# panner.net
KiCad netlist of a schematic drawn in EAGLE
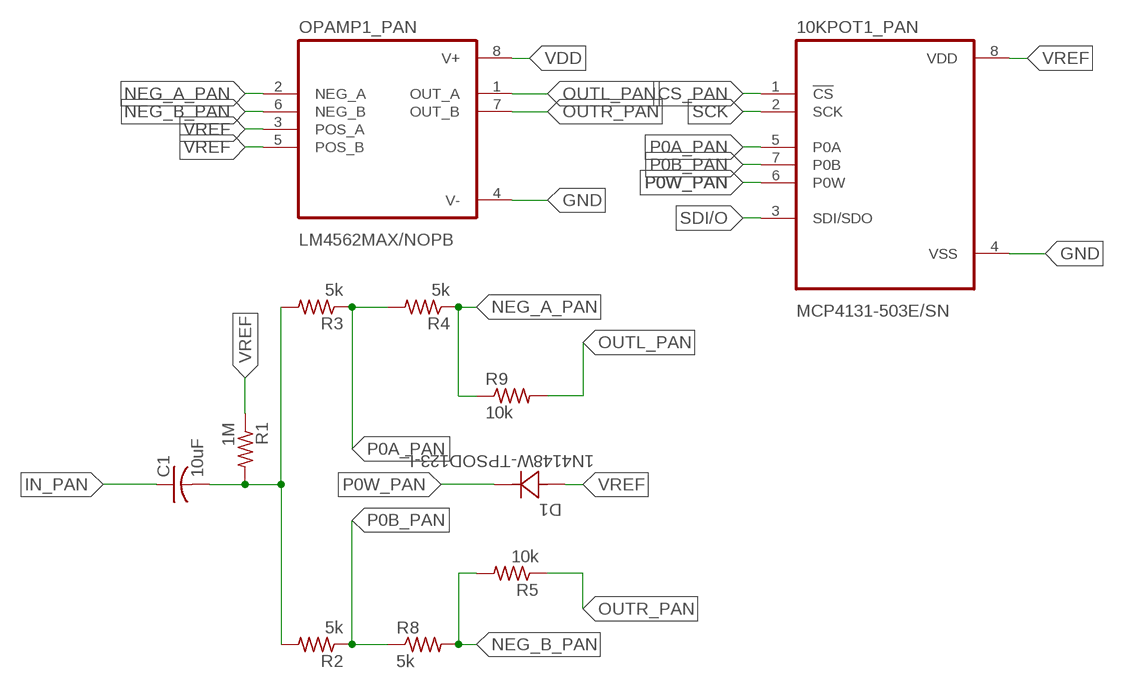
[diagram p0: schematic, sheet 1]

(export (version "E")
  (design (tool "Eeschema 10.0.6"))
  (components
    (comp (ref "10KPOT1_PAN")
      (value "MCP4131-503E/SN")
      (footprint "eagle-import:SOIC127P599X175-8N")
      (fields (field (name "MF") "Microchip") (field (name "SPICEPREFIX") "X"))
      (libsource (lib "eagle-import") (part "MCP4131-503E/SN"))
    )
    (comp (ref "C1")
      (value "10uF")
      (footprint "eagle-import:C0402")
      (libsource (lib "eagle-import") (part "C-USC0402"))
    )
    (comp (ref "D1")
      (value "1N4148W-TPSOD123-L")
      (footprint "eagle-import:SOD123-L")
      (fields (field (name "MF") "Micro Commercial") (field (name "MP") "1N4148W-TP"))
      (libsource (lib "eagle-import") (part "1N4148W-TPSOD123-L"))
    )
    (comp (ref "OPAMP1_PAN")
      (value "LM4562MAX/NOPB")
      (footprint "eagle-import:SOIC127P599X175-8N")
      (fields (field (name "MF") "Texas Instruments"))
      (libsource (lib "eagle-import") (part "LM4562MAX/NOPB"))
    )
    (comp (ref "R1")
      (value "1M")
      (footprint "eagle-import:R0402")
      (libsource (lib "eagle-import") (part "R-US_R0402"))
    )
    (comp (ref "R2")
      (value "5k")
      (footprint "eagle-import:R0402")
      (libsource (lib "eagle-import") (part "R-US_R0402"))
    )
    (comp (ref "R3")
      (value "5k")
      (footprint "eagle-import:R0402")
      (libsource (lib "eagle-import") (part "R-US_R0402"))
    )
    (comp (ref "R4")
      (value "5k")
      (footprint "eagle-import:R0402")
      (libsource (lib "eagle-import") (part "R-US_R0402"))
    )
    (comp (ref "R5")
      (value "10k")
      (footprint "eagle-import:R0402")
      (libsource (lib "eagle-import") (part "R-US_R0402"))
    )
    (comp (ref "R8")
      (value "5k")
      (footprint "eagle-import:R0402")
      (libsource (lib "eagle-import") (part "R-US_R0402"))
    )
    (comp (ref "R9")
      (value "10k")
      (footprint "eagle-import:R0402")
      (libsource (lib "eagle-import") (part "R-US_R0402"))
    )
  )
  (nets
    (net (code "1") (name "CS_PAN") (class "Default")
      (node (ref "10KPOT1_PAN") (pin "1") (pinfunction "~{CS}_1") (pintype "input"))
    )
    (net (code "2") (name "GND") (class "Default")
      (node (ref "10KPOT1_PAN") (pin "4") (pinfunction "VSS_4") (pintype "power_in"))
      (node (ref "OPAMP1_PAN") (pin "4") (pinfunction "V-_4") (pintype "power_in"))
    )
    (net (code "3") (name "IN_PAN") (class "Default")
      (node (ref "C1") (pin "1") (pinfunction "1_1") (pintype "passive"))
    )
    (net (code "4") (name "NEG_A_PAN") (class "Default")
      (node (ref "OPAMP1_PAN") (pin "2") (pinfunction "NEG_A_2") (pintype "input"))
      (node (ref "R4") (pin "1") (pinfunction "1_1") (pintype "passive"))
      (node (ref "R9") (pin "1") (pinfunction "1_1") (pintype "passive"))
    )
    (net (code "5") (name "NEG_B_PAN") (class "Default")
      (node (ref "OPAMP1_PAN") (pin "6") (pinfunction "NEG_B_6") (pintype "input"))
      (node (ref "R5") (pin "2") (pinfunction "2_2") (pintype "passive"))
      (node (ref "R8") (pin "2") (pinfunction "2_2") (pintype "passive"))
    )
    (net (code "6") (name "Net-(C1-Pad2)") (class "Default")
      (node (ref "C1") (pin "2") (pinfunction "2_2") (pintype "passive"))
      (node (ref "R1") (pin "2") (pinfunction "2_2") (pintype "passive"))
      (node (ref "R2") (pin "2") (pinfunction "2_2") (pintype "passive"))
      (node (ref "R3") (pin "2") (pinfunction "2_2") (pintype "passive"))
    )
    (net (code "7") (name "OUTL_PAN") (class "Default")
      (node (ref "OPAMP1_PAN") (pin "1") (pinfunction "OUT_A_1") (pintype "output"))
      (node (ref "R9") (pin "2") (pinfunction "2_2") (pintype "passive"))
    )
    (net (code "8") (name "OUTR_PAN") (class "Default")
      (node (ref "OPAMP1_PAN") (pin "7") (pinfunction "OUT_B_7") (pintype "output"))
      (node (ref "R5") (pin "1") (pinfunction "1_1") (pintype "passive"))
    )
    (net (code "9") (name "P0A_PAN") (class "Default")
      (node (ref "10KPOT1_PAN") (pin "5") (pinfunction "P0A_5") (pintype "bidirectional"))
      (node (ref "R3") (pin "1") (pinfunction "1_1") (pintype "passive"))
      (node (ref "R4") (pin "2") (pinfunction "2_2") (pintype "passive"))
    )
    (net (code "10") (name "P0B_PAN") (class "Default")
      (node (ref "10KPOT1_PAN") (pin "7") (pinfunction "P0B_7") (pintype "bidirectional"))
      (node (ref "R2") (pin "1") (pinfunction "1_1") (pintype "passive"))
      (node (ref "R8") (pin "1") (pinfunction "1_1") (pintype "passive"))
    )
    (net (code "11") (name "P0W_PAN") (class "Default")
      (node (ref "10KPOT1_PAN") (pin "6") (pinfunction "P0W_6") (pintype "bidirectional"))
      (node (ref "D1") (pin "1") (pinfunction "C_1") (pintype "passive"))
    )
    (net (code "12") (name "SCK") (class "Default")
      (node (ref "10KPOT1_PAN") (pin "2") (pinfunction "SCK_2") (pintype "input"))
    )
    (net (code "13") (name "SDI{slash}O") (class "Default")
      (node (ref "10KPOT1_PAN") (pin "3") (pinfunction "SDI/SDO_3") (pintype "bidirectional"))
    )
    (net (code "14") (name "VDD") (class "Default")
      (node (ref "OPAMP1_PAN") (pin "8") (pinfunction "V+_8") (pintype "power_in"))
    )
    (net (code "15") (name "VREF") (class "Default")
      (node (ref "10KPOT1_PAN") (pin "8") (pinfunction "VDD_8") (pintype "power_in"))
      (node (ref "D1") (pin "2") (pinfunction "A_2") (pintype "passive"))
      (node (ref "OPAMP1_PAN") (pin "3") (pinfunction "POS_A_3") (pintype "input"))
      (node (ref "OPAMP1_PAN") (pin "5") (pinfunction "POS_B_5") (pintype "input"))
      (node (ref "R1") (pin "1") (pinfunction "1_1") (pintype "passive"))
    )
  )
)
